# Hote.net
KiCad netlist of a schematic drawn in EAGLE
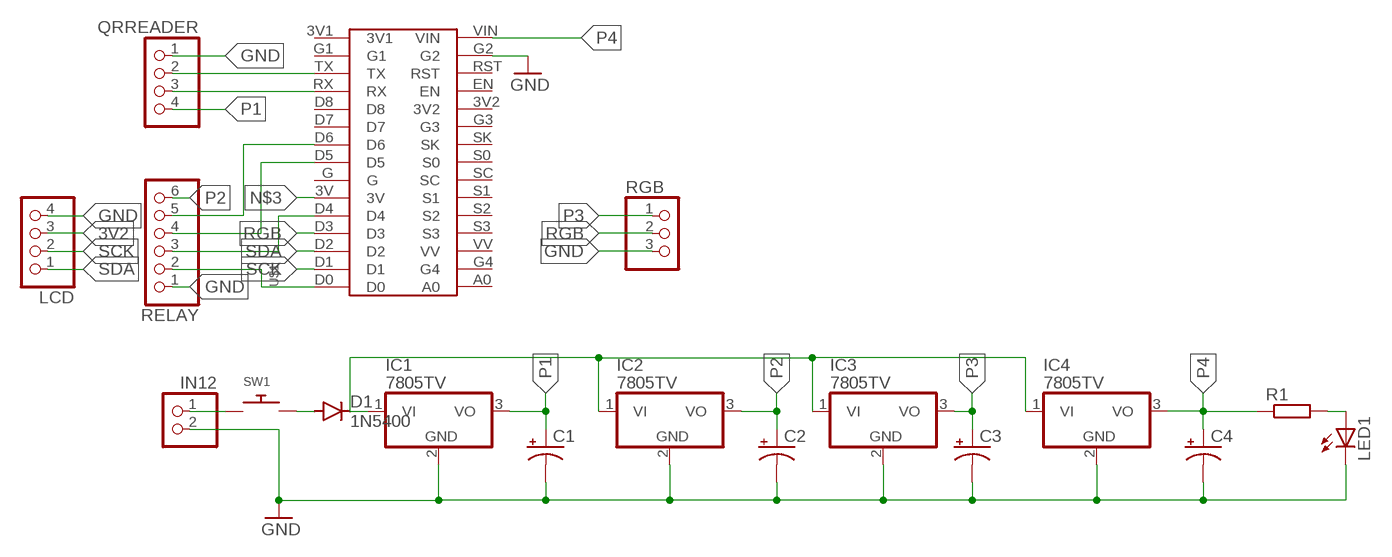
[diagram p0: schematic, sheet 1]

(export (version "E")
  (design (tool "Eeschema 10.0.6"))
  (components
    (comp (ref "C1")
      (value "CPOL-USTT5D9")
      (footprint "eagle-import:TT5D9")
      (libsource (lib "eagle-import") (part "CPOL-USTT5D9"))
    )
    (comp (ref "C2")
      (value "CPOL-USTT5D9")
      (footprint "eagle-import:TT5D9")
      (libsource (lib "eagle-import") (part "CPOL-USTT5D9"))
    )
    (comp (ref "C3")
      (value "CPOL-USTT5D9")
      (footprint "eagle-import:TT5D9")
      (libsource (lib "eagle-import") (part "CPOL-USTT5D9"))
    )
    (comp (ref "C4")
      (value "CPOL-USTT5D9")
      (footprint "eagle-import:TT5D9")
      (libsource (lib "eagle-import") (part "CPOL-USTT5D9"))
    )
    (comp (ref "D1")
      (value "1N5400")
      (footprint "eagle-import:DO201-15")
      (libsource (lib "eagle-import") (part "1N5400"))
    )
    (comp (ref "IC1")
      (value "7805TV")
      (footprint "eagle-import:TO220V")
      (libsource (lib "eagle-import") (part "78TV05"))
    )
    (comp (ref "IC2")
      (value "7805TV")
      (footprint "eagle-import:TO220V")
      (libsource (lib "eagle-import") (part "78TV05"))
    )
    (comp (ref "IC3")
      (value "7805TV")
      (footprint "eagle-import:TO220V")
      (libsource (lib "eagle-import") (part "78TV05"))
    )
    (comp (ref "IC4")
      (value "7805TV")
      (footprint "eagle-import:TO220V")
      (libsource (lib "eagle-import") (part "78TV05"))
    )
    (comp (ref "IN12")
      (value "PINHD-1X2")
      (footprint "eagle-import:1X02")
      (libsource (lib "eagle-import") (part "PINHD-1X2"))
    )
    (comp (ref "LCD")
      (value "PINHD-1X4")
      (footprint "eagle-import:1X04")
      (libsource (lib "eagle-import") (part "PINHD-1X4"))
    )
    (comp (ref "LED1")
      (value "LED5MM")
      (footprint "eagle-import:LED5MM")
      (libsource (lib "eagle-import") (part "LED5MM"))
    )
    (comp (ref "QRREADER")
      (value "PINHD-1X4")
      (footprint "eagle-import:1X04")
      (libsource (lib "eagle-import") (part "PINHD-1X4"))
    )
    (comp (ref "R1")
      (value "R-EU_0204/7")
      (footprint "eagle-import:0204_7")
      (libsource (lib "eagle-import") (part "R-EU_0204/7"))
    )
    (comp (ref "RELAY")
      (value "PINHD-1X6")
      (footprint "eagle-import:1X06")
      (libsource (lib "eagle-import") (part "PINHD-1X6"))
    )
    (comp (ref "RGB")
      (value "PINHD-1X3")
      (footprint "eagle-import:1X03")
      (libsource (lib "eagle-import") (part "PINHD-1X3"))
    )
    (comp (ref "SW1")
      (value "SWITCH_PUSHBUTTONEVQ-PE")
      (footprint "eagle-import:TACT_PANA-EVQ")
      (libsource (lib "eagle-import") (part "SWITCH_PUSHBUTTONEVQ-PE"))
    )
    (comp (ref "U$1")
      (value "LOLIN")
      (footprint "eagle-import:LOLIN")
      (libsource (lib "eagle-import") (part "LOLIN"))
    )
  )
  (nets
    (net (code "1") (name "3V2") (class "Default")
      (node (ref "LCD") (pin "3") (pinfunction "3_3") (pintype "passive"))
    )
    (net (code "2") (name "GND") (class "Default")
      (node (ref "C1") (pin "-") (pinfunction "-_-") (pintype "passive"))
      (node (ref "C2") (pin "-") (pinfunction "-_-") (pintype "passive"))
      (node (ref "C3") (pin "-") (pinfunction "-_-") (pintype "passive"))
      (node (ref "C4") (pin "-") (pinfunction "-_-") (pintype "passive"))
      (node (ref "IC1") (pin "2") (pinfunction "GND_2") (pintype "passive"))
      (node (ref "IC2") (pin "2") (pinfunction "GND_2") (pintype "passive"))
      (node (ref "IC3") (pin "2") (pinfunction "GND_2") (pintype "passive"))
      (node (ref "IC4") (pin "2") (pinfunction "GND_2") (pintype "passive"))
      (node (ref "IN12") (pin "2") (pinfunction "2_2") (pintype "passive"))
      (node (ref "LCD") (pin "4") (pinfunction "4_4") (pintype "passive"))
      (node (ref "LED1") (pin "K") (pinfunction "C_K") (pintype "passive"))
      (node (ref "QRREADER") (pin "1") (pinfunction "1_1") (pintype "passive"))
      (node (ref "RELAY") (pin "1") (pinfunction "1_1") (pintype "passive"))
      (node (ref "RGB") (pin "3") (pinfunction "3_3") (pintype "passive"))
      (node (ref "U$1") (pin "G2") (pinfunction "G2_G2") (pintype "bidirectional"))
    )
    (net (code "3") (name "N$3") (class "Default")
      (node (ref "U$1") (pin "3V") (pinfunction "3V_3V") (pintype "bidirectional"))
    )
    (net (code "4") (name "Net-(D1-PadA)") (class "Default")
      (node (ref "D1") (pin "A") (pinfunction "A_A") (pintype "passive"))
      (node (ref "SW1") (pin "P$2") (pinfunction "P$2_P$2") (pintype "passive"))
    )
    (net (code "5") (name "Net-(IC1-VI)") (class "Default")
      (node (ref "D1") (pin "C") (pinfunction "C_C") (pintype "passive"))
      (node (ref "IC1") (pin "1") (pinfunction "VI_1") (pintype "input"))
      (node (ref "IC2") (pin "1") (pinfunction "VI_1") (pintype "input"))
      (node (ref "IC3") (pin "1") (pinfunction "VI_1") (pintype "input"))
      (node (ref "IC4") (pin "1") (pinfunction "VI_1") (pintype "input"))
    )
    (net (code "6") (name "Net-(IN12-Pad1)") (class "Default")
      (node (ref "IN12") (pin "1") (pinfunction "1_1") (pintype "passive"))
      (node (ref "SW1") (pin "P$1") (pinfunction "P$1_P$1") (pintype "passive"))
    )
    (net (code "7") (name "Net-(LED1-PadA)") (class "Default")
      (node (ref "LED1") (pin "A") (pinfunction "A_A") (pintype "passive"))
      (node (ref "R1") (pin "2") (pinfunction "2_2") (pintype "passive"))
    )
    (net (code "8") (name "Net-(QRREADER-Pad2)") (class "Default")
      (node (ref "QRREADER") (pin "2") (pinfunction "2_2") (pintype "passive"))
      (node (ref "U$1") (pin "TX") (pinfunction "TX_TX") (pintype "bidirectional"))
    )
    (net (code "9") (name "Net-(QRREADER-Pad3)") (class "Default")
      (node (ref "QRREADER") (pin "3") (pinfunction "3_3") (pintype "passive"))
      (node (ref "U$1") (pin "RX") (pinfunction "RX_RX") (pintype "bidirectional"))
    )
    (net (code "10") (name "Net-(RELAY-Pad2)") (class "Default")
      (node (ref "RELAY") (pin "2") (pinfunction "2_2") (pintype "passive"))
      (node (ref "U$1") (pin "D0") (pinfunction "D0_D0") (pintype "bidirectional"))
    )
    (net (code "11") (name "Net-(RELAY-Pad3)") (class "Default")
      (node (ref "RELAY") (pin "3") (pinfunction "3_3") (pintype "passive"))
      (node (ref "U$1") (pin "D4") (pinfunction "D4_D4") (pintype "bidirectional"))
    )
    (net (code "12") (name "Net-(RELAY-Pad4)") (class "Default")
      (node (ref "RELAY") (pin "4") (pinfunction "4_4") (pintype "passive"))
      (node (ref "U$1") (pin "D5") (pinfunction "D5_D5") (pintype "bidirectional"))
    )
    (net (code "13") (name "Net-(RELAY-Pad5)") (class "Default")
      (node (ref "RELAY") (pin "5") (pinfunction "5_5") (pintype "passive"))
      (node (ref "U$1") (pin "D6") (pinfunction "D6_D6") (pintype "bidirectional"))
    )
    (net (code "14") (name "P1") (class "Default")
      (node (ref "C1") (pin "+") (pinfunction "+_+") (pintype "passive"))
      (node (ref "IC1") (pin "3") (pinfunction "VO_3") (pintype "passive"))
      (node (ref "QRREADER") (pin "4") (pinfunction "4_4") (pintype "passive"))
    )
    (net (code "15") (name "P2") (class "Default")
      (node (ref "C2") (pin "+") (pinfunction "+_+") (pintype "passive"))
      (node (ref "IC2") (pin "3") (pinfunction "VO_3") (pintype "passive"))
      (node (ref "RELAY") (pin "6") (pinfunction "6_6") (pintype "passive"))
    )
    (net (code "16") (name "P3") (class "Default")
      (node (ref "C3") (pin "+") (pinfunction "+_+") (pintype "passive"))
      (node (ref "IC3") (pin "3") (pinfunction "VO_3") (pintype "passive"))
      (node (ref "RGB") (pin "1") (pinfunction "1_1") (pintype "passive"))
    )
    (net (code "17") (name "P4") (class "Default")
      (node (ref "C4") (pin "+") (pinfunction "+_+") (pintype "passive"))
      (node (ref "IC4") (pin "3") (pinfunction "VO_3") (pintype "passive"))
      (node (ref "R1") (pin "1") (pinfunction "1_1") (pintype "passive"))
      (node (ref "U$1") (pin "VIN") (pinfunction "VIN_VIN") (pintype "bidirectional"))
    )
    (net (code "18") (name "RGB") (class "Default")
      (node (ref "RGB") (pin "2") (pinfunction "2_2") (pintype "passive"))
      (node (ref "U$1") (pin "D3") (pinfunction "D3_D3") (pintype "bidirectional"))
    )
    (net (code "19") (name "SCK") (class "Default")
      (node (ref "LCD") (pin "2") (pinfunction "2_2") (pintype "passive"))
      (node (ref "U$1") (pin "D1") (pinfunction "D1_D1") (pintype "bidirectional"))
    )
    (net (code "20") (name "SDA") (class "Default")
      (node (ref "LCD") (pin "1") (pinfunction "1_1") (pintype "passive"))
      (node (ref "U$1") (pin "D2") (pinfunction "D2_D2") (pintype "bidirectional"))
    )
    (net (code "21") (name "unconnected-(U$1-Pad3V1)") (class "Default")
      (node (ref "U$1") (pin "3V1") (pinfunction "3V1_3V1") (pintype "bidirectional"))
    )
    (net (code "22") (name "unconnected-(U$1-Pad3V2)") (class "Default")
      (node (ref "U$1") (pin "3V2") (pinfunction "3V2_3V2") (pintype "bidirectional"))
    )
    (net (code "23") (name "unconnected-(U$1-PadA0)") (class "Default")
      (node (ref "U$1") (pin "A0") (pinfunction "A0_A0") (pintype "bidirectional"))
    )
    (net (code "24") (name "unconnected-(U$1-PadD7)") (class "Default")
      (node (ref "U$1") (pin "D7") (pinfunction "D7_D7") (pintype "bidirectional"))
    )
    (net (code "25") (name "unconnected-(U$1-PadD8)") (class "Default")
      (node (ref "U$1") (pin "D8") (pinfunction "D8_D8") (pintype "bidirectional"))
    )
    (net (code "26") (name "unconnected-(U$1-PadEN)") (class "Default")
      (node (ref "U$1") (pin "EN") (pinfunction "EN_EN") (pintype "bidirectional"))
    )
    (net (code "27") (name "unconnected-(U$1-PadG)") (class "Default")
      (node (ref "U$1") (pin "G") (pinfunction "G_G") (pintype "bidirectional"))
    )
    (net (code "28") (name "unconnected-(U$1-PadG1)") (class "Default")
      (node (ref "U$1") (pin "G1") (pinfunction "G1_G1") (pintype "bidirectional"))
    )
    (net (code "29") (name "unconnected-(U$1-PadG3)") (class "Default")
      (node (ref "U$1") (pin "G3") (pinfunction "G3_G3") (pintype "bidirectional"))
    )
    (net (code "30") (name "unconnected-(U$1-PadG4)") (class "Default")
      (node (ref "U$1") (pin "G4") (pinfunction "G4_G4") (pintype "bidirectional"))
    )
    (net (code "31") (name "unconnected-(U$1-PadRST)") (class "Default")
      (node (ref "U$1") (pin "RST") (pinfunction "RST_RST") (pintype "bidirectional"))
    )
    (net (code "32") (name "unconnected-(U$1-PadS0)") (class "Default")
      (node (ref "U$1") (pin "S0") (pinfunction "S0_S0") (pintype "bidirectional"))
    )
    (net (code "33") (name "unconnected-(U$1-PadS1)") (class "Default")
      (node (ref "U$1") (pin "S1") (pinfunction "S1_S1") (pintype "bidirectional"))
    )
    (net (code "34") (name "unconnected-(U$1-PadS2)") (class "Default")
      (node (ref "U$1") (pin "S2") (pinfunction "S2_S2") (pintype "bidirectional"))
    )
    (net (code "35") (name "unconnected-(U$1-PadS3)") (class "Default")
      (node (ref "U$1") (pin "S3") (pinfunction "S3_S3") (pintype "bidirectional"))
    )
    (net (code "36") (name "unconnected-(U$1-PadSC)") (class "Default")
      (node (ref "U$1") (pin "SC") (pinfunction "SC_SC") (pintype "bidirectional"))
    )
    (net (code "37") (name "unconnected-(U$1-PadSK)") (class "Default")
      (node (ref "U$1") (pin "SK") (pinfunction "SK_SK") (pintype "bidirectional"))
    )
    (net (code "38") (name "unconnected-(U$1-PadVV)") (class "Default")
      (node (ref "U$1") (pin "VV") (pinfunction "VV_VV") (pintype "bidirectional"))
    )
  )
)
